# stoplight_v1_0.net
KiCad netlist of a schematic drawn in Altium Designer
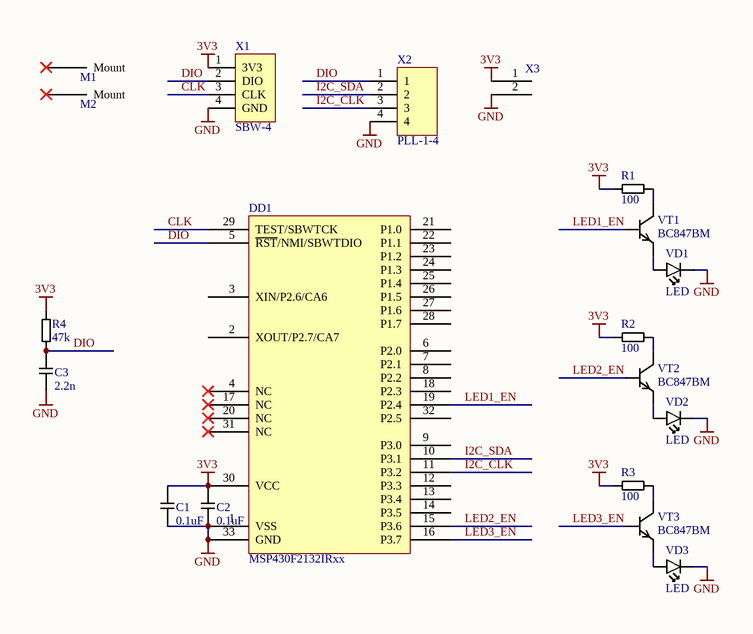
[diagram p0: stoplight_v1.0.SchDoc]

(export (version "E")
  (design (tool "Eeschema 10.0.6"))
  (components
    (comp (ref "C1") (value "0.1uF") (footprint "C0603") (libsource (lib "passive") (part "C")))
    (comp (ref "C2") (value "0.1uF") (footprint "C0603") (libsource (lib "passive") (part "C")))
    (comp (ref "C3") (value "2.2n") (footprint "C0603") (libsource (lib "passive") (part "C")))
    (comp (ref "DD1")
      (value "MSP430F2132IRxx")
      (footprint "QFN-32 5x5 0.5")
      (description "TI 16bit MCU MSP430 series")
      (libsource (lib "msp430") (part "MSP430F2132IRxx"))
    )
    (comp (ref "M1")
      (value "MountHoleEmpty")
      (footprint "MountHole 2mm Empty")
      (description "Mounting hole without metallization")
      (libsource (lib "connectors") (part "MountHoleEmpty"))
    )
    (comp (ref "M2")
      (value "MountHoleEmpty")
      (footprint "MountHole 2mm Empty")
      (description "Mounting hole without metallization")
      (libsource (lib "connectors") (part "MountHoleEmpty"))
    )
    (comp (ref "R1") (value "100") (footprint "R0603") (libsource (lib "passive") (part "R")))
    (comp (ref "R2") (value "100") (footprint "R0603") (libsource (lib "passive") (part "R")))
    (comp (ref "R3") (value "100") (footprint "R0603") (libsource (lib "passive") (part "R")))
    (comp (ref "R4") (value "47k") (footprint "R0603") (libsource (lib "passive") (part "R")))
    (comp (ref "VD1")
      (value "LED")
      (footprint "LED0603")
      (description "SMD LED")
      (libsource (lib "led") (part "LED"))
    )
    (comp (ref "VD2")
      (value "LED")
      (footprint "LED0603")
      (description "SMD LED")
      (libsource (lib "led") (part "LED"))
    )
    (comp (ref "VD3")
      (value "LED")
      (footprint "LED0603")
      (description "SMD LED")
      (libsource (lib "led") (part "LED"))
    )
    (comp (ref "VT1")
      (value "BC847BM")
      (footprint "SOT-883")
      (description "SOT-883 bipolar transistor hfe=290")
      (libsource (lib "transistors") (part "BC847BM"))
    )
    (comp (ref "VT2")
      (value "BC847BM")
      (footprint "SOT-883")
      (description "SOT-883 bipolar transistor hfe=290")
      (libsource (lib "transistors") (part "BC847BM"))
    )
    (comp (ref "VT3")
      (value "BC847BM")
      (footprint "SOT-883")
      (description "SOT-883 bipolar transistor hfe=290")
      (libsource (lib "transistors") (part "BC847BM"))
    )
    (comp (ref "X1")
      (value "SBW-4")
      (footprint "PLL-1-4")
      (description "TI MSP430 SpyByWire connector")
      (libsource (lib "connectors") (part "SBW-4"))
    )
    (comp (ref "X2")
      (value "PLL-1-4")
      (footprint "PLL-1-4")
      (description "1.27mm pin header")
      (libsource (lib "connectors") (part "PLL-1-4"))
    )
    (comp (ref "X3")
      (value "POWER_PINS")
      (footprint "POWER_PINS")
      (description "On board power pins")
      (libsource (lib "stoplight") (part "POWER_PINS"))
    )
  )
  (nets
    (net (code "1") (name "/CLK") (class "Default")
      (node (ref "DD1") (pin "29") (pinfunction "TEST/SBWTCK_29") (pintype "passive"))
      (node (ref "X1") (pin "3") (pinfunction "CLK_3") (pintype "passive"))
    )
    (net (code "2") (name "/DIO") (class "Default")
      (node (ref "C3") (pin "1") (pinfunction "1_1") (pintype "passive"))
      (node (ref "DD1") (pin "5") (pinfunction "~{RST}/NMI/SBWTDIO_5") (pintype "passive"))
      (node (ref "R4") (pin "2") (pinfunction "2_2") (pintype "passive"))
      (node (ref "X1") (pin "2") (pinfunction "DIO_2") (pintype "passive"))
      (node (ref "X2") (pin "1") (pinfunction "1_1") (pintype "passive"))
    )
    (net (code "3") (name "/I2C_CLK") (class "Default")
      (node (ref "DD1") (pin "11") (pinfunction "P3.2_11") (pintype "passive"))
      (node (ref "X2") (pin "3") (pinfunction "3_3") (pintype "passive"))
    )
    (net (code "4") (name "/I2C_SDA") (class "Default")
      (node (ref "DD1") (pin "10") (pinfunction "P3.1_10") (pintype "passive"))
      (node (ref "X2") (pin "2") (pinfunction "2_2") (pintype "passive"))
    )
    (net (code "5") (name "/LED1_EN") (class "Default")
      (node (ref "DD1") (pin "19") (pinfunction "P2.4_19") (pintype "passive"))
      (node (ref "VT1") (pin "1") (pinfunction "B_1") (pintype "passive"))
    )
    (net (code "6") (name "/LED2_EN") (class "Default")
      (node (ref "DD1") (pin "15") (pinfunction "P3.6_15") (pintype "passive"))
      (node (ref "VT2") (pin "1") (pinfunction "B_1") (pintype "passive"))
    )
    (net (code "7") (name "/LED3_EN") (class "Default")
      (node (ref "DD1") (pin "16") (pinfunction "P3.7_16") (pintype "passive"))
      (node (ref "VT3") (pin "1") (pinfunction "B_1") (pintype "passive"))
    )
    (net (code "8") (name "3V3") (class "Default")
      (node (ref "C1") (pin "1") (pinfunction "1_1") (pintype "passive"))
      (node (ref "C2") (pin "1") (pinfunction "1_1") (pintype "passive"))
      (node (ref "DD1") (pin "30") (pinfunction "VCC_30") (pintype "passive"))
      (node (ref "R1") (pin "1") (pinfunction "1_1") (pintype "passive"))
      (node (ref "R2") (pin "1") (pinfunction "1_1") (pintype "passive"))
      (node (ref "R3") (pin "1") (pinfunction "1_1") (pintype "passive"))
      (node (ref "R4") (pin "1") (pinfunction "1_1") (pintype "passive"))
      (node (ref "X1") (pin "1") (pinfunction "3V3_1") (pintype "passive"))
      (node (ref "X3") (pin "1") (pinfunction "A_1") (pintype "passive"))
    )
    (net (code "9") (name "GND") (class "Default")
      (node (ref "C1") (pin "2") (pinfunction "2_2") (pintype "passive"))
      (node (ref "C2") (pin "2") (pinfunction "2_2") (pintype "passive"))
      (node (ref "C3") (pin "2") (pinfunction "2_2") (pintype "passive"))
      (node (ref "DD1") (pin "1") (pinfunction "VSS_1") (pintype "passive"))
      (node (ref "DD1") (pin "33") (pinfunction "GND_33") (pintype "passive"))
      (node (ref "VD1") (pin "1") (pinfunction "1_1") (pintype "passive"))
      (node (ref "VD2") (pin "1") (pinfunction "1_1") (pintype "passive"))
      (node (ref "VD3") (pin "1") (pinfunction "1_1") (pintype "passive"))
      (node (ref "X1") (pin "4") (pinfunction "GND_4") (pintype "passive"))
      (node (ref "X2") (pin "4") (pinfunction "4_4") (pintype "passive"))
      (node (ref "X3") (pin "2") (pinfunction "B_2") (pintype "passive"))
    )
    (net (code "10") (name "Net-(VT1-C)") (class "Default")
      (node (ref "R1") (pin "2") (pinfunction "2_2") (pintype "passive"))
      (node (ref "VT1") (pin "3") (pinfunction "C_3") (pintype "passive"))
    )
    (net (code "11") (name "Net-(VT1-E)") (class "Default")
      (node (ref "VD1") (pin "2") (pinfunction "2_2") (pintype "passive"))
      (node (ref "VT1") (pin "2") (pinfunction "E_2") (pintype "passive"))
    )
    (net (code "12") (name "Net-(VT2-C)") (class "Default")
      (node (ref "R2") (pin "2") (pinfunction "2_2") (pintype "passive"))
      (node (ref "VT2") (pin "3") (pinfunction "C_3") (pintype "passive"))
    )
    (net (code "13") (name "Net-(VT2-E)") (class "Default")
      (node (ref "VD2") (pin "2") (pinfunction "2_2") (pintype "passive"))
      (node (ref "VT2") (pin "2") (pinfunction "E_2") (pintype "passive"))
    )
    (net (code "14") (name "Net-(VT3-C)") (class "Default")
      (node (ref "R3") (pin "2") (pinfunction "2_2") (pintype "passive"))
      (node (ref "VT3") (pin "3") (pinfunction "C_3") (pintype "passive"))
    )
    (net (code "15") (name "Net-(VT3-E)") (class "Default")
      (node (ref "VD3") (pin "2") (pinfunction "2_2") (pintype "passive"))
      (node (ref "VT3") (pin "2") (pinfunction "E_2") (pintype "passive"))
    )
    (net (code "16") (name "unconnected-(DD1-NC-Pad4)") (class "Default")
      (node (ref "DD1") (pin "4") (pinfunction "NC_4") (pintype "passive+no_connect"))
    )
    (net (code "17") (name "unconnected-(DD1-NC-Pad17)") (class "Default")
      (node (ref "DD1") (pin "17") (pinfunction "NC_17") (pintype "passive+no_connect"))
    )
    (net (code "18") (name "unconnected-(DD1-NC-Pad20)") (class "Default")
      (node (ref "DD1") (pin "20") (pinfunction "NC_20") (pintype "passive+no_connect"))
    )
    (net (code "19") (name "unconnected-(DD1-NC-Pad31)") (class "Default")
      (node (ref "DD1") (pin "31") (pinfunction "NC_31") (pintype "passive+no_connect"))
    )
    (net (code "20") (name "unconnected-(DD1-P1.0-Pad21)") (class "Default")
      (node (ref "DD1") (pin "21") (pinfunction "P1.0_21") (pintype "passive"))
    )
    (net (code "21") (name "unconnected-(DD1-P1.1-Pad22)") (class "Default")
      (node (ref "DD1") (pin "22") (pinfunction "P1.1_22") (pintype "passive"))
    )
    (net (code "22") (name "unconnected-(DD1-P1.2-Pad23)") (class "Default")
      (node (ref "DD1") (pin "23") (pinfunction "P1.2_23") (pintype "passive"))
    )
    (net (code "23") (name "unconnected-(DD1-P1.3-Pad24)") (class "Default")
      (node (ref "DD1") (pin "24") (pinfunction "P1.3_24") (pintype "passive"))
    )
    (net (code "24") (name "unconnected-(DD1-P1.4-Pad25)") (class "Default")
      (node (ref "DD1") (pin "25") (pinfunction "P1.4_25") (pintype "passive"))
    )
    (net (code "25") (name "unconnected-(DD1-P1.5-Pad26)") (class "Default")
      (node (ref "DD1") (pin "26") (pinfunction "P1.5_26") (pintype "passive"))
    )
    (net (code "26") (name "unconnected-(DD1-P1.6-Pad27)") (class "Default")
      (node (ref "DD1") (pin "27") (pinfunction "P1.6_27") (pintype "passive"))
    )
    (net (code "27") (name "unconnected-(DD1-P1.7-Pad28)") (class "Default")
      (node (ref "DD1") (pin "28") (pinfunction "P1.7_28") (pintype "passive"))
    )
    (net (code "28") (name "unconnected-(DD1-P2.0-Pad6)") (class "Default")
      (node (ref "DD1") (pin "6") (pinfunction "P2.0_6") (pintype "passive"))
    )
    (net (code "29") (name "unconnected-(DD1-P2.1-Pad7)") (class "Default")
      (node (ref "DD1") (pin "7") (pinfunction "P2.1_7") (pintype "passive"))
    )
    (net (code "30") (name "unconnected-(DD1-P2.2-Pad8)") (class "Default")
      (node (ref "DD1") (pin "8") (pinfunction "P2.2_8") (pintype "passive"))
    )
    (net (code "31") (name "unconnected-(DD1-P2.3-Pad18)") (class "Default")
      (node (ref "DD1") (pin "18") (pinfunction "P2.3_18") (pintype "passive"))
    )
    (net (code "32") (name "unconnected-(DD1-P2.5-Pad32)") (class "Default")
      (node (ref "DD1") (pin "32") (pinfunction "P2.5_32") (pintype "passive"))
    )
    (net (code "33") (name "unconnected-(DD1-P3.0-Pad9)") (class "Default")
      (node (ref "DD1") (pin "9") (pinfunction "P3.0_9") (pintype "passive"))
    )
    (net (code "34") (name "unconnected-(DD1-P3.3-Pad12)") (class "Default")
      (node (ref "DD1") (pin "12") (pinfunction "P3.3_12") (pintype "passive"))
    )
    (net (code "35") (name "unconnected-(DD1-P3.4-Pad13)") (class "Default")
      (node (ref "DD1") (pin "13") (pinfunction "P3.4_13") (pintype "passive"))
    )
    (net (code "36") (name "unconnected-(DD1-P3.5-Pad14)") (class "Default")
      (node (ref "DD1") (pin "14") (pinfunction "P3.5_14") (pintype "passive"))
    )
    (net (code "37") (name "unconnected-(DD1-XIN{slash}P2.6{slash}CA6-Pad3)") (class "Default")
      (node (ref "DD1") (pin "3") (pinfunction "XIN/P2.6/CA6_3") (pintype "passive"))
    )
    (net (code "38") (name "unconnected-(DD1-XOUT{slash}P2.7{slash}CA7-Pad2)") (class "Default")
      (node (ref "DD1") (pin "2") (pinfunction "XOUT/P2.7/CA7_2") (pintype "passive"))
    )
    (net (code "39") (name "unconnected-(M1-Mount-Pad1)") (class "Default")
      (node (ref "M1") (pin "1") (pinfunction "Mount_1") (pintype "passive+no_connect"))
    )
    (net (code "40") (name "unconnected-(M2-Mount-Pad1)") (class "Default")
      (node (ref "M2") (pin "1") (pinfunction "Mount_1") (pintype "passive+no_connect"))
    )
  )
)
